# ProDoc_P1_2025-06-26.net
KiCad netlist of a schematic drawn in EasyEDA Pro
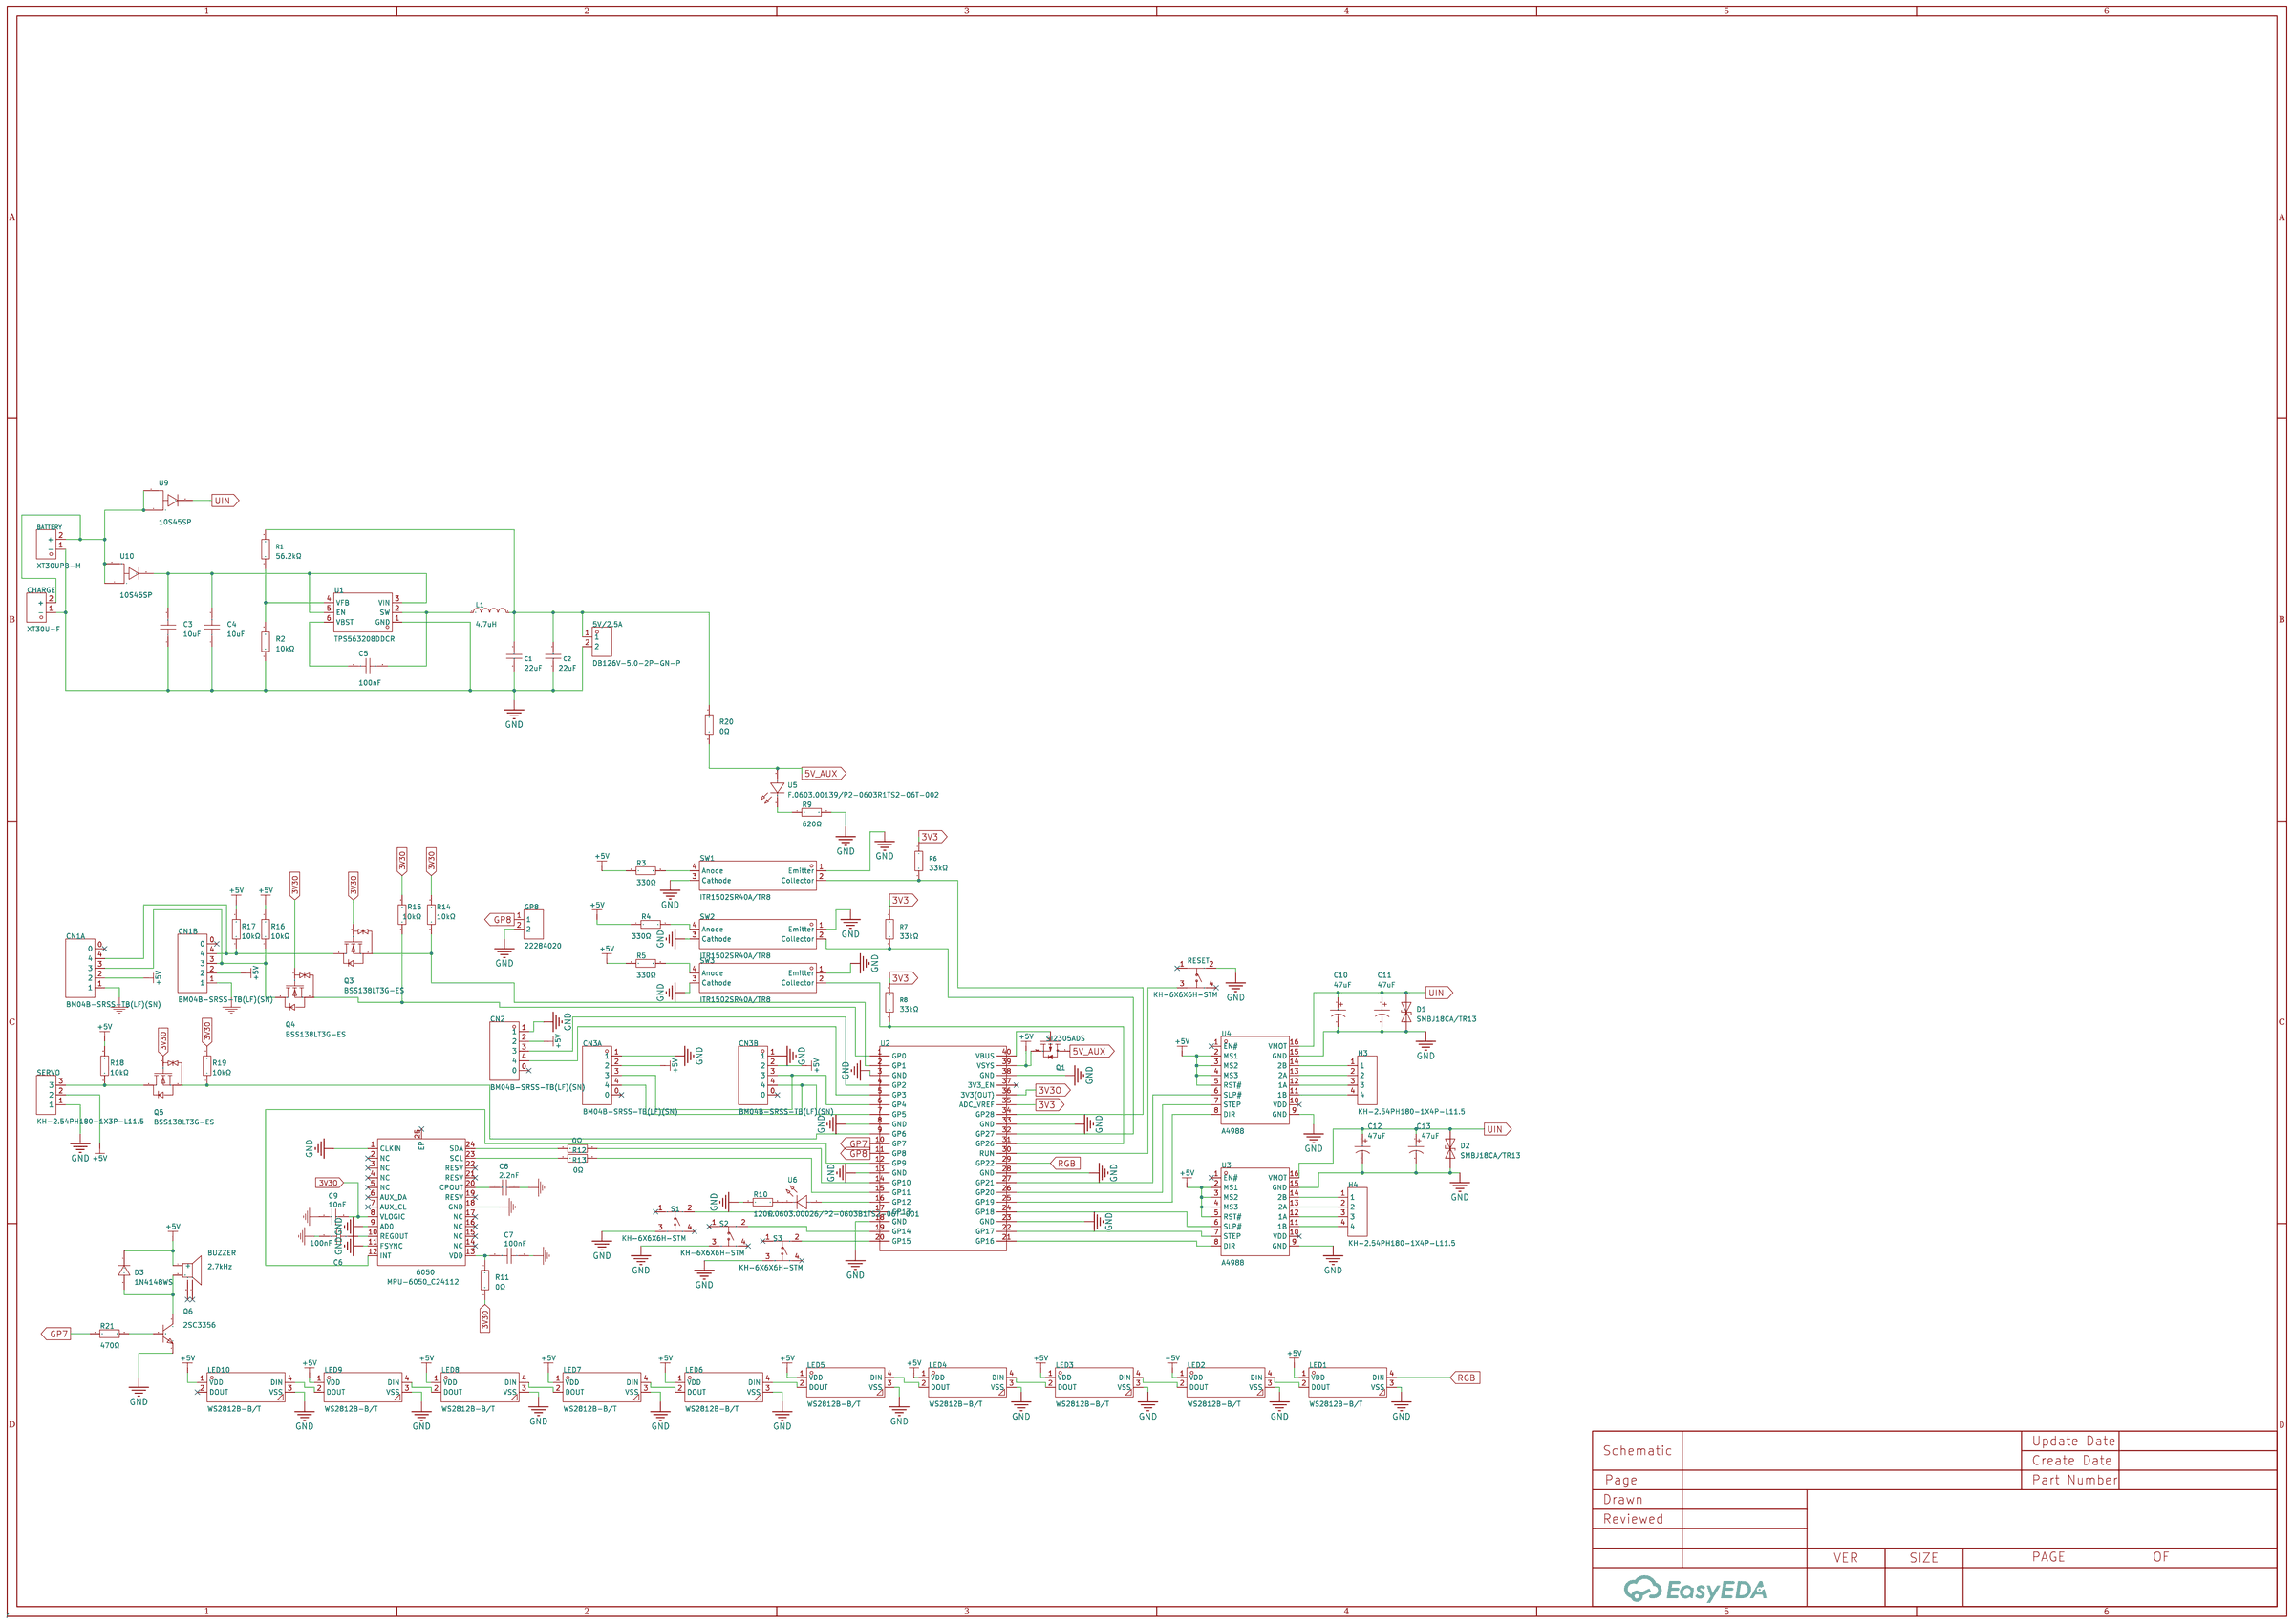
[diagram p0: schematic sheet]

(export (version "E")
  (design (tool "Eeschema 10.0.6"))
  (components
    (comp (ref "5V/2.5A")
      (value "DB126V-5.0-2P-GN-P")
      (footprint "easyedapro:CONN-TH_2P-P5.00_L7.8-W10.0")
      (fields (field (name "Manufacturer") "DORABO(地博电气)"))
      (libsource (lib "easyedapro") (part "DB126V-5.0-2P"))
    )
    (comp (ref "6050")
      (value "MPU-6050_C24112")
      (footprint "easyedapro:QFN-24_L4.0-W4.0-P0.50-BL-EP2.7")
      (fields
        (field (name "Manufacturer Part") "MPU-6050")
        (field (name "Manufacturer") "TDK InvenSense(应美盛)")
      )
      (libsource (lib "easyedapro") (part "MPU-6050_C24112"))
    )
    (comp (ref "BATTERY")
      (value "XT30UPB-M")
      (footprint "easyedapro:CONN-TH_XT30UPB-M")
      (fields (field (name "Manufacturer") "AMASS(艾迈斯)"))
      (libsource (lib "easyedapro") (part "XT30UPB-M"))
    )
    (comp (ref "BUZZER")
      (value "2.7kHz")
      (footprint "easyedapro:BUZ-SMD_4P-L8.5-W8.5-P8.50-BR")
      (fields (field (name "Manufacturer Part") "MLT-8530") (field (name "Manufacturer") "华能"))
      (libsource (lib "easyedapro") (part "MLT-8530"))
    )
    (comp (ref "C1")
      (value "22uF")
      (footprint "easyedapro:C1210")
      (fields
        (field (name "Manufacturer Part") "GRM32ER61E226KE15L")
        (field (name "Manufacturer") "muRata(村田)")
      )
      (libsource (lib "easyedapro") (part "GRM32ER61E226KE15L"))
    )
    (comp (ref "C2")
      (value "22uF")
      (footprint "easyedapro:C1210")
      (fields
        (field (name "Manufacturer Part") "GRM32ER61E226KE15L")
        (field (name "Manufacturer") "muRata(村田)")
      )
      (libsource (lib "easyedapro") (part "GRM32ER61E226KE15L"))
    )
    (comp (ref "C3")
      (value "10uF")
      (footprint "easyedapro:C1206")
      (fields
        (field (name "Manufacturer Part") "GRM31CR61E106KA12L")
        (field (name "Manufacturer") "muRata(村田)")
      )
      (libsource (lib "easyedapro") (part "GRM31CR61E106KA12L"))
    )
    (comp (ref "C4")
      (value "10uF")
      (footprint "easyedapro:C1206")
      (fields
        (field (name "Manufacturer Part") "GRM31CR61E106KA12L")
        (field (name "Manufacturer") "muRata(村田)")
      )
      (libsource (lib "easyedapro") (part "GRM31CR61E106KA12L"))
    )
    (comp (ref "C5")
      (value "100nF")
      (footprint "easyedapro:C0603")
      (fields
        (field (name "Manufacturer Part") "GRM188R71H104KA93D")
        (field (name "Manufacturer") "muRata(村田)")
      )
      (libsource (lib "easyedapro") (part "GRM188R71H104KA93D"))
    )
    (comp (ref "C6")
      (value "100nF")
      (footprint "easyedapro:C0603")
      (fields
        (field (name "Manufacturer Part") "CL10B104KB8NNNC")
        (field (name "Manufacturer") "SAMSUNG(三星)")
      )
      (libsource (lib "easyedapro") (part "100nF"))
    )
    (comp (ref "C7")
      (value "100nF")
      (footprint "easyedapro:C0603")
      (fields
        (field (name "Manufacturer Part") "CL10B104KB8NNNC")
        (field (name "Manufacturer") "SAMSUNG(三星)")
      )
      (libsource (lib "easyedapro") (part "100nF"))
    )
    (comp (ref "C8")
      (value "2.2nF")
      (footprint "easyedapro:C0603")
      (fields (field (name "Manufacturer Part") "0603B222K500NT") (field (name "Manufacturer") "FH(风华)"))
      (libsource (lib "easyedapro") (part "2.2nF"))
    )
    (comp (ref "C9")
      (value "10nF")
      (footprint "easyedapro:C0603")
      (fields
        (field (name "Manufacturer Part") "CL10B103KB8NNNC")
        (field (name "Manufacturer") "SAMSUNG(三星)")
      )
      (libsource (lib "easyedapro") (part "10nF"))
    )
    (comp (ref "C10")
      (value "47uF")
      (footprint "easyedapro:CAP-TH_BD6.3-P2.50-D1.0-FD")
      (fields
        (field (name "Manufacturer Part") "SPZ1HM470E08O00RAXXX")
        (field (name "Manufacturer") "AISHI(艾华集团)")
      )
      (libsource (lib "easyedapro") (part "SPZ1HM470E08000R"))
    )
    (comp (ref "C11")
      (value "47uF")
      (footprint "easyedapro:CAP-TH_BD6.3-P2.50-D1.0-FD")
      (fields
        (field (name "Manufacturer Part") "SPZ1HM470E08O00RAXXX")
        (field (name "Manufacturer") "AISHI(艾华集团)")
      )
      (libsource (lib "easyedapro") (part "SPZ1HM470E08000R"))
    )
    (comp (ref "C12")
      (value "47uF")
      (footprint "easyedapro:CAP-TH_BD6.3-P2.50-D1.0-FD")
      (fields
        (field (name "Manufacturer Part") "SPZ1HM470E08O00RAXXX")
        (field (name "Manufacturer") "AISHI(艾华集团)")
      )
      (libsource (lib "easyedapro") (part "SPZ1HM470E08000R"))
    )
    (comp (ref "C13")
      (value "47uF")
      (footprint "easyedapro:CAP-TH_BD6.3-P2.50-D1.0-FD")
      (fields
        (field (name "Manufacturer Part") "SPZ1HM470E08O00RAXXX")
        (field (name "Manufacturer") "AISHI(艾华集团)")
      )
      (libsource (lib "easyedapro") (part "SPZ1HM470E08000R"))
    )
    (comp (ref "CHARGE")
      (value "XT30U-F")
      (footprint "easyedapro:CONN-TH_XT30U-F")
      (fields (field (name "Manufacturer") "AMASS(艾迈斯)"))
      (libsource (lib "easyedapro") (part "XT30U-F"))
    )
    (comp (ref "CN1A")
      (value "BM04B-SRSS-TB(LF)(SN)")
      (footprint "easyedapro:CONN-SMD_BM04B-SRSS-TB")
      (fields (field (name "Manufacturer") "JST"))
      (libsource (lib "easyedapro") (part "BM04B-SRSS-TB(LF)(SN)"))
    )
    (comp (ref "CN1B")
      (value "BM04B-SRSS-TB(LF)(SN)")
      (footprint "easyedapro:CONN-SMD_BM04B-SRSS-TB")
      (fields (field (name "Manufacturer") "JST"))
      (libsource (lib "easyedapro") (part "BM04B-SRSS-TB(LF)(SN)"))
    )
    (comp (ref "CN2")
      (value "BM04B-SRSS-TB(LF)(SN)")
      (footprint "easyedapro:CONN-SMD_BM04B-SRSS-TB")
      (fields (field (name "Manufacturer") "JST"))
      (libsource (lib "") (part "BM04B-SRSS-TB(LF)(SN)_1"))
    )
    (comp (ref "CN3A")
      (value "BM04B-SRSS-TB(LF)(SN)")
      (footprint "easyedapro:CONN-SMD_BM04B-SRSS-TB")
      (fields (field (name "Manufacturer") "JST"))
      (libsource (lib "") (part "BM04B-SRSS-TB(LF)(SN)_1"))
    )
    (comp (ref "CN3B")
      (value "BM04B-SRSS-TB(LF)(SN)")
      (footprint "easyedapro:CONN-SMD_BM04B-SRSS-TB")
      (fields (field (name "Manufacturer") "JST"))
      (libsource (lib "") (part "BM04B-SRSS-TB(LF)(SN)_1"))
    )
    (comp (ref "D1")
      (value "SMBJ18CA/TR13")
      (footprint "easyedapro:SMB_L4.6-W3.6-LS5.3-BI")
      (fields (field (name "Manufacturer") "Brightking(君耀电子)"))
      (libsource (lib "easyedapro") (part "SMBJ18CA-C78413"))
    )
    (comp (ref "D2")
      (value "SMBJ18CA/TR13")
      (footprint "easyedapro:SMB_L4.6-W3.6-LS5.3-BI")
      (fields (field (name "Manufacturer") "Brightking(君耀电子)"))
      (libsource (lib "easyedapro") (part "SMBJ18CA-C78413"))
    )
    (comp (ref "D3")
      (value "1N4148WS")
      (footprint "easyedapro:SOD-323_L1.8-W1.3-LS2.5-RD")
      (fields (field (name "Manufacturer") "CJ(江苏长电/长晶)"))
      (libsource (lib "easyedapro") (part "1N4148WS T4"))
    )
    (comp (ref "GP8")
      (value "22284020")
      (footprint "easyedapro:HDR-TH_2P-P2.54-V-M-1")
      (fields (field (name "Manufacturer") "MOLEX"))
      (libsource (lib "easyedapro") (part "22-28-4020"))
    )
    (comp (ref "H3")
      (value "KH-2.54PH180-1X4P-L11.5")
      (footprint "easyedapro:HDR-TH_4P-P2.54-V-M")
      (fields (field (name "Manufacturer") "kinghelm(金航标)"))
      (libsource (lib "easyedapro") (part "KH-2.54PH180-1X4P-L11.5"))
    )
    (comp (ref "H4")
      (value "KH-2.54PH180-1X4P-L11.5")
      (footprint "easyedapro:HDR-TH_4P-P2.54-V-M")
      (fields (field (name "Manufacturer") "kinghelm(金航标)"))
      (libsource (lib "easyedapro") (part "KH-2.54PH180-1X4P-L11.5"))
    )
    (comp (ref "L1")
      (value "4.7uH")
      (footprint "easyedapro:IND-SMD_L7.0-W6.6")
      (fields (field (name "Manufacturer Part") "FXL0630-4R7-M") (field (name "Manufacturer") "cjiang(长江微电)"))
      (libsource (lib "easyedapro") (part "FXL0630-4R7-M"))
    )
    (comp (ref "LED1")
      (value "WS2812B-B/T")
      (footprint "easyedapro:LED-SMD_4P-L5.0-W5.0-TL_WS2812B-B")
      (fields (field (name "Manufacturer") "worldsemi"))
      (libsource (lib "easyedapro") (part "WS2812B-B/W"))
    )
    (comp (ref "LED2")
      (value "WS2812B-B/T")
      (footprint "easyedapro:LED-SMD_4P-L5.0-W5.0-TL_WS2812B-B")
      (fields (field (name "Manufacturer") "worldsemi"))
      (libsource (lib "easyedapro") (part "WS2812B-B/W"))
    )
    (comp (ref "LED3")
      (value "WS2812B-B/T")
      (footprint "easyedapro:LED-SMD_4P-L5.0-W5.0-TL_WS2812B-B")
      (fields (field (name "Manufacturer") "worldsemi"))
      (libsource (lib "easyedapro") (part "WS2812B-B/W"))
    )
    (comp (ref "LED4")
      (value "WS2812B-B/T")
      (footprint "easyedapro:LED-SMD_4P-L5.0-W5.0-TL_WS2812B-B")
      (fields (field (name "Manufacturer") "worldsemi"))
      (libsource (lib "easyedapro") (part "WS2812B-B/W"))
    )
    (comp (ref "LED5")
      (value "WS2812B-B/T")
      (footprint "easyedapro:LED-SMD_4P-L5.0-W5.0-TL_WS2812B-B")
      (fields (field (name "Manufacturer") "worldsemi"))
      (libsource (lib "easyedapro") (part "WS2812B-B/W"))
    )
    (comp (ref "LED6")
      (value "WS2812B-B/T")
      (footprint "easyedapro:LED-SMD_4P-L5.0-W5.0-TL_WS2812B-B")
      (fields (field (name "Manufacturer") "worldsemi"))
      (libsource (lib "easyedapro") (part "WS2812B-B/W"))
    )
    (comp (ref "LED7")
      (value "WS2812B-B/T")
      (footprint "easyedapro:LED-SMD_4P-L5.0-W5.0-TL_WS2812B-B")
      (fields (field (name "Manufacturer") "worldsemi"))
      (libsource (lib "easyedapro") (part "WS2812B-B/W"))
    )
    (comp (ref "LED8")
      (value "WS2812B-B/T")
      (footprint "easyedapro:LED-SMD_4P-L5.0-W5.0-TL_WS2812B-B")
      (fields (field (name "Manufacturer") "worldsemi"))
      (libsource (lib "easyedapro") (part "WS2812B-B/W"))
    )
    (comp (ref "LED9")
      (value "WS2812B-B/T")
      (footprint "easyedapro:LED-SMD_4P-L5.0-W5.0-TL_WS2812B-B")
      (fields (field (name "Manufacturer") "worldsemi"))
      (libsource (lib "easyedapro") (part "WS2812B-B/W"))
    )
    (comp (ref "LED10")
      (value "WS2812B-B/T")
      (footprint "easyedapro:LED-SMD_4P-L5.0-W5.0-TL_WS2812B-B")
      (fields (field (name "Manufacturer") "worldsemi"))
      (libsource (lib "easyedapro") (part "WS2812B-B/W"))
    )
    (comp (ref "Q1")
      (value "SI2305ADS")
      (footprint "easyedapro:SOT-23-3_L2.9-W1.3-P1.90-LS2.4-BR")
      (fields (field (name "Manufacturer") "TECH PUBLIC(台舟)"))
      (libsource (lib "easyedapro") (part "SI2305ADS"))
    )
    (comp (ref "Q3")
      (value "BSS138LT3G-ES")
      (footprint "easyedapro:SOT-23-3_L2.9-W1.3-P1.90-LS2.4-BR")
      (fields (field (name "Manufacturer") "ElecSuper(静芯微)"))
      (libsource (lib "easyedapro") (part "BSS138LT3G-ES"))
    )
    (comp (ref "Q4")
      (value "BSS138LT3G-ES")
      (footprint "easyedapro:SOT-23-3_L2.9-W1.3-P1.90-LS2.4-BR")
      (fields (field (name "Manufacturer") "ElecSuper(静芯微)"))
      (libsource (lib "easyedapro") (part "BSS138LT3G-ES"))
    )
    (comp (ref "Q5")
      (value "BSS138LT3G-ES")
      (footprint "easyedapro:SOT-23-3_L2.9-W1.3-P1.90-LS2.4-BR")
      (fields (field (name "Manufacturer") "ElecSuper(静芯微)"))
      (libsource (lib "easyedapro") (part "BSS138LT3G-ES"))
    )
    (comp (ref "Q6")
      (value "2SC3356")
      (footprint "easyedapro:SOT-23-3_L2.9-W1.3-P1.90-LS2.4-BR")
      (fields (field (name "Manufacturer") "宏嘉诚"))
      (libsource (lib "easyedapro") (part "2SC3356_C28646266"))
    )
    (comp (ref "R1")
      (value "56.2kΩ")
      (footprint "easyedapro:R0402")
      (fields
        (field (name "Manufacturer Part") "0402WGF5622TCE")
        (field (name "Manufacturer") "UNI-ROYAL(厚声)")
      )
      (libsource (lib "easyedapro") (part "0402WGF5622TCE"))
    )
    (comp (ref "R2")
      (value "10kΩ")
      (footprint "easyedapro:R0402")
      (fields
        (field (name "Manufacturer Part") "0402WGF1002TCE")
        (field (name "Manufacturer") "UNI-ROYAL(厚声)")
      )
      (libsource (lib "easyedapro") (part "0402WGF1002TCE"))
    )
    (comp (ref "R3")
      (value "330Ω")
      (footprint "easyedapro:R0603")
      (fields
        (field (name "Manufacturer Part") "0603WAF3300T5E")
        (field (name "Manufacturer") "UNI-ROYAL(厚声)")
      )
      (libsource (lib "easyedapro") (part "0603WAF3300T5E"))
    )
    (comp (ref "R4")
      (value "330Ω")
      (footprint "easyedapro:R0603")
      (fields
        (field (name "Manufacturer Part") "0603WAF3300T5E")
        (field (name "Manufacturer") "UNI-ROYAL(厚声)")
      )
      (libsource (lib "easyedapro") (part "0603WAF3300T5E"))
    )
    (comp (ref "R5")
      (value "330Ω")
      (footprint "easyedapro:R0603")
      (fields
        (field (name "Manufacturer Part") "0603WAF3300T5E")
        (field (name "Manufacturer") "UNI-ROYAL(厚声)")
      )
      (libsource (lib "easyedapro") (part "0603WAF3300T5E"))
    )
    (comp (ref "R6")
      (value "33kΩ")
      (footprint "easyedapro:R0603")
      (fields
        (field (name "Manufacturer Part") "0603WAF3302T5E")
        (field (name "Manufacturer") "UNI-ROYAL(厚声)")
      )
      (libsource (lib "easyedapro") (part "0603WAF3302T5E"))
    )
    (comp (ref "R7")
      (value "33kΩ")
      (footprint "easyedapro:R0603")
      (fields
        (field (name "Manufacturer Part") "0603WAF3302T5E")
        (field (name "Manufacturer") "UNI-ROYAL(厚声)")
      )
      (libsource (lib "easyedapro") (part "0603WAF3302T5E"))
    )
    (comp (ref "R8")
      (value "33kΩ")
      (footprint "easyedapro:R0603")
      (fields
        (field (name "Manufacturer Part") "0603WAF3302T5E")
        (field (name "Manufacturer") "UNI-ROYAL(厚声)")
      )
      (libsource (lib "easyedapro") (part "0603WAF3302T5E"))
    )
    (comp (ref "R9")
      (value "620Ω")
      (footprint "easyedapro:R0603")
      (fields (field (name "Manufacturer Part") "RC0603FR-07620RL") (field (name "Manufacturer") "YAGEO(国巨)"))
      (libsource (lib "easyedapro") (part "RC0603FR-07620RL"))
    )
    (comp (ref "R10")
      (value "120Ω")
      (footprint "easyedapro:R0603")
      (fields (field (name "Manufacturer Part") "RC0603FR-07120RL") (field (name "Manufacturer") "YAGEO(国巨)"))
      (libsource (lib "easyedapro") (part "RC0603FR-07120RL"))
    )
    (comp (ref "R11")
      (value "0Ω")
      (footprint "easyedapro:R0603")
      (fields
        (field (name "Manufacturer Part") "0603WAJ0000T5E")
        (field (name "Manufacturer") "UNI-ROYAL(厚声)")
      )
      (libsource (lib "easyedapro") (part "0Ω"))
    )
    (comp (ref "R12")
      (value "0Ω")
      (footprint "easyedapro:R0603")
      (fields
        (field (name "Manufacturer Part") "0603WAJ0000T5E")
        (field (name "Manufacturer") "UNI-ROYAL(厚声)")
      )
      (libsource (lib "easyedapro") (part "0Ω"))
    )
    (comp (ref "R13")
      (value "0Ω")
      (footprint "easyedapro:R0603")
      (fields
        (field (name "Manufacturer Part") "0603WAJ0000T5E")
        (field (name "Manufacturer") "UNI-ROYAL(厚声)")
      )
      (libsource (lib "easyedapro") (part "0Ω"))
    )
    (comp (ref "R14")
      (value "10kΩ")
      (footprint "easyedapro:R0603")
      (fields (field (name "Manufacturer Part") "AC0603FR-0710KL") (field (name "Manufacturer") "YAGEO(国巨)"))
      (libsource (lib "easyedapro") (part "10kΩ"))
    )
    (comp (ref "R15")
      (value "10kΩ")
      (footprint "easyedapro:R0603")
      (fields (field (name "Manufacturer Part") "AC0603FR-0710KL") (field (name "Manufacturer") "YAGEO(国巨)"))
      (libsource (lib "easyedapro") (part "10kΩ"))
    )
    (comp (ref "R16")
      (value "10kΩ")
      (footprint "easyedapro:R0603")
      (fields (field (name "Manufacturer Part") "AC0603FR-0710KL") (field (name "Manufacturer") "YAGEO(国巨)"))
      (libsource (lib "easyedapro") (part "10kΩ"))
    )
    (comp (ref "R17")
      (value "10kΩ")
      (footprint "easyedapro:R0603")
      (fields (field (name "Manufacturer Part") "AC0603FR-0710KL") (field (name "Manufacturer") "YAGEO(国巨)"))
      (libsource (lib "easyedapro") (part "10kΩ"))
    )
    (comp (ref "R18")
      (value "10kΩ")
      (footprint "easyedapro:R0603")
      (fields (field (name "Manufacturer Part") "AC0603FR-0710KL") (field (name "Manufacturer") "YAGEO(国巨)"))
      (libsource (lib "easyedapro") (part "10kΩ"))
    )
    (comp (ref "R19")
      (value "10kΩ")
      (footprint "easyedapro:R0603")
      (fields (field (name "Manufacturer Part") "AC0603FR-0710KL") (field (name "Manufacturer") "YAGEO(国巨)"))
      (libsource (lib "easyedapro") (part "10kΩ"))
    )
    (comp (ref "R20")
      (value "0Ω")
      (footprint "easyedapro:R0603")
      (fields
        (field (name "Manufacturer Part") "0603WAJ0000T5E")
        (field (name "Manufacturer") "UNI-ROYAL(厚声)")
      )
      (libsource (lib "easyedapro") (part "0Ω"))
    )
    (comp (ref "R21")
      (value "470Ω")
      (footprint "easyedapro:R0603")
      (fields
        (field (name "Manufacturer Part") "0603WAF4700T5E")
        (field (name "Manufacturer") "UNI-ROYAL(厚声)")
      )
      (libsource (lib "easyedapro") (part "0603WAF4700T5E"))
    )
    (comp (ref "RESET")
      (value "KH-6X6X6H-STM")
      (footprint "easyedapro:SW-SMD_4P-L6.0-W6.0-P4.50-LS9.0-3")
      (fields (field (name "Manufacturer") "kinghelm(金航标)"))
      (libsource (lib "easyedapro") (part "KH-6X6X6H-STM"))
    )
    (comp (ref "S1")
      (value "KH-6X6X6H-STM")
      (footprint "easyedapro:SW-SMD_4P-L6.0-W6.0-P4.50-LS9.0-3")
      (fields (field (name "Manufacturer") "kinghelm(金航标)"))
      (libsource (lib "easyedapro") (part "KH-6X6X6H-STM"))
    )
    (comp (ref "S2")
      (value "KH-6X6X6H-STM")
      (footprint "easyedapro:SW-SMD_4P-L6.0-W6.0-P4.50-LS9.0-3")
      (fields (field (name "Manufacturer") "kinghelm(金航标)"))
      (libsource (lib "easyedapro") (part "KH-6X6X6H-STM"))
    )
    (comp (ref "S3")
      (value "KH-6X6X6H-STM")
      (footprint "easyedapro:SW-SMD_4P-L6.0-W6.0-P4.50-LS9.0-3")
      (fields (field (name "Manufacturer") "kinghelm(金航标)"))
      (libsource (lib "easyedapro") (part "KH-6X6X6H-STM"))
    )
    (comp (ref "SERVO")
      (value "KH-2.54PH180-1X3P-L11.5")
      (footprint "easyedapro:HDR-TH_3P-P2.54-V-M")
      (fields (field (name "Manufacturer") "kinghelm(金航标)"))
      (libsource (lib "easyedapro") (part "KH-2.54PH180-1X3P-L11.5"))
    )
    (comp (ref "SW1")
      (value "ITR1502SR40A/TR8")
      (footprint "easyedapro:SW-SMD_4P-L4.0-W3.0_ITR1502SR40A-TR8")
      (fields (field (name "Manufacturer") "EVERLIGHT(亿光)"))
      (libsource (lib "easyedapro") (part "ITR1502SR40A/TR8"))
    )
    (comp (ref "SW2")
      (value "ITR1502SR40A/TR8")
      (footprint "easyedapro:SW-SMD_4P-L4.0-W3.0_ITR1502SR40A-TR8")
      (fields (field (name "Manufacturer") "EVERLIGHT(亿光)"))
      (libsource (lib "easyedapro") (part "ITR1502SR40A/TR8"))
    )
    (comp (ref "SW3")
      (value "ITR1502SR40A/TR8")
      (footprint "easyedapro:SW-SMD_4P-L4.0-W3.0_ITR1502SR40A-TR8")
      (fields (field (name "Manufacturer") "EVERLIGHT(亿光)"))
      (libsource (lib "easyedapro") (part "ITR1502SR40A/TR8"))
    )
    (comp (ref "U1")
      (value "TPS563208DDCR")
      (footprint "easyedapro:TSOT-23-6_L2.9-W1.6-P0.95-LS2.8-BL")
      (fields (field (name "Manufacturer") "TI(德州仪器)"))
      (libsource (lib "easyedapro") (part "TPS563208DDCR"))
    )
    (comp (ref "U2")
      (value "~")
      (footprint "easyedapro:RPI_PICO_DIL")
      (description "Raspberry pi pico in DIL")
      (libsource (lib "easyedapro") (part "RPI_PICO_DIL"))
    )
    (comp (ref "U3")
      (value "A4988")
      (footprint "easyedapro:DIP-16_L20.3-W15.2-P2.54_LS12.7_A4988")
      (libsource (lib "easyedapro") (part "A4988"))
    )
    (comp (ref "U4")
      (value "A4988")
      (footprint "easyedapro:DIP-16_L20.3-W15.2-P2.54_LS12.7_A4988")
      (libsource (lib "easyedapro") (part "A4988"))
    )
    (comp (ref "U5")
      (value "F.0603.00139/P2-0603R1TS2-06T-002")
      (footprint "easyedapro:LED0603-RD")
      (fields (field (name "Manufacturer") "TUOZHAN(拓展光电)"))
      (libsource (lib "easyedapro") (part "F.0603.00139/P2-0603R1TS2-06T-002"))
    )
    (comp (ref "U6")
      (value "F.0603.00026/P2-0603B1TS2-06T-001")
      (footprint "easyedapro:LED0603-RD")
      (fields (field (name "Manufacturer") "TUOZHAN(拓展光电)"))
      (libsource (lib "easyedapro") (part "F.0603.00026/P2-0603B1TS2-06T-001"))
    )
    (comp (ref "U9")
      (value "10S45SP")
      (footprint "easyedapro:TO-277_3P-L5.4-W4.0-LS6.5-TR-1")
      (fields (field (name "Manufacturer") "YFW(佑风微)"))
      (libsource (lib "easyedapro") (part "10S45SP"))
    )
    (comp (ref "U10")
      (value "10S45SP")
      (footprint "easyedapro:TO-277_3P-L5.4-W4.0-LS6.5-TR-1")
      (fields (field (name "Manufacturer") "YFW(佑风微)"))
      (libsource (lib "easyedapro") (part "10S45SP"))
    )
  )
  (nets
    (net (code "1") (name "+5V") (class "Default")
      (node (ref "BUZZER") (pin "1") (pinfunction "+_1") (pintype "unspecified"))
      (node (ref "CN1A") (pin "2") (pinfunction "2_2") (pintype "unspecified"))
      (node (ref "CN1B") (pin "2") (pinfunction "2_2") (pintype "unspecified"))
      (node (ref "CN2") (pin "2") (pinfunction "2_2") (pintype "unspecified"))
      (node (ref "CN3A") (pin "2") (pinfunction "2_2") (pintype "unspecified"))
      (node (ref "CN3B") (pin "2") (pinfunction "2_2") (pintype "unspecified"))
      (node (ref "D3") (pin "1") (pinfunction "K_1") (pintype "unspecified"))
      (node (ref "LED1") (pin "1") (pinfunction "VDD_1") (pintype "unspecified"))
      (node (ref "LED10") (pin "1") (pinfunction "VDD_1") (pintype "unspecified"))
      (node (ref "LED2") (pin "1") (pinfunction "VDD_1") (pintype "unspecified"))
      (node (ref "LED3") (pin "1") (pinfunction "VDD_1") (pintype "unspecified"))
      (node (ref "LED4") (pin "1") (pinfunction "VDD_1") (pintype "unspecified"))
      (node (ref "LED5") (pin "1") (pinfunction "VDD_1") (pintype "unspecified"))
      (node (ref "LED6") (pin "1") (pinfunction "VDD_1") (pintype "unspecified"))
      (node (ref "LED7") (pin "1") (pinfunction "VDD_1") (pintype "unspecified"))
      (node (ref "LED8") (pin "1") (pinfunction "VDD_1") (pintype "unspecified"))
      (node (ref "LED9") (pin "1") (pinfunction "VDD_1") (pintype "unspecified"))
      (node (ref "Q1") (pin "2") (pinfunction "S_2") (pintype "unspecified"))
      (node (ref "R16") (pin "2") (pinfunction "2_2") (pintype "input"))
      (node (ref "R17") (pin "2") (pinfunction "2_2") (pintype "input"))
      (node (ref "R18") (pin "2") (pinfunction "2_2") (pintype "input"))
      (node (ref "R3") (pin "1") (pinfunction "1_1") (pintype "input"))
      (node (ref "R4") (pin "1") (pinfunction "1_1") (pintype "input"))
      (node (ref "R5") (pin "1") (pinfunction "1_1") (pintype "input"))
      (node (ref "SERVO") (pin "2") (pinfunction "2_2") (pintype "unspecified"))
      (node (ref "U2") (pin "39") (pinfunction "VSYS_39") (pintype "input"))
      (node (ref "U3") (pin "2") (pinfunction "MS1_2") (pintype "unspecified"))
      (node (ref "U3") (pin "3") (pinfunction "MS2_3") (pintype "unspecified"))
      (node (ref "U3") (pin "4") (pinfunction "MS3_4") (pintype "unspecified"))
      (node (ref "U3") (pin "5") (pinfunction "RST#_5") (pintype "unspecified"))
      (node (ref "U4") (pin "2") (pinfunction "MS1_2") (pintype "unspecified"))
      (node (ref "U4") (pin "3") (pinfunction "MS2_3") (pintype "unspecified"))
      (node (ref "U4") (pin "4") (pinfunction "MS3_4") (pintype "unspecified"))
      (node (ref "U4") (pin "5") (pinfunction "RST#_5") (pintype "unspecified"))
    )
    (net (code "2") (name "3V3") (class "Default")
      (node (ref "R6") (pin "1") (pinfunction "1_1") (pintype "input"))
      (node (ref "R7") (pin "1") (pinfunction "1_1") (pintype "input"))
      (node (ref "R8") (pin "2") (pinfunction "2_2") (pintype "input"))
      (node (ref "U2") (pin "35") (pinfunction "ADC_VREF_35") (pintype "input"))
    )
    (net (code "3") (name "3V3O") (class "Default")
      (node (ref "6050") (pin "8") (pinfunction "VLOGIC_8") (pintype "unspecified"))
      (node (ref "C9") (pin "2") (pinfunction "2_2") (pintype "input"))
      (node (ref "Q3") (pin "1") (pinfunction "G_1") (pintype "unspecified"))
      (node (ref "Q4") (pin "1") (pinfunction "G_1") (pintype "unspecified"))
      (node (ref "Q5") (pin "1") (pinfunction "G_1") (pintype "unspecified"))
      (node (ref "R11") (pin "2") (pinfunction "2_2") (pintype "input"))
      (node (ref "R14") (pin "2") (pinfunction "2_2") (pintype "input"))
      (node (ref "R15") (pin "2") (pinfunction "2_2") (pintype "input"))
      (node (ref "R19") (pin "2") (pinfunction "2_2") (pintype "input"))
      (node (ref "U2") (pin "36") (pinfunction "3V3(OUT)_36") (pintype "input"))
    )
    (net (code "4") (name "5V_AUX") (class "Default")
      (node (ref "Q1") (pin "3") (pinfunction "D_3") (pintype "unspecified"))
      (node (ref "R20") (pin "2") (pinfunction "2_2") (pintype "input"))
      (node (ref "U5") (pin "2") (pinfunction "A_2") (pintype "unspecified"))
    )
    (net (code "5") (name "GND") (class "Default")
      (node (ref "5V/2.5A") (pin "2") (pinfunction "2_2") (pintype "unspecified"))
      (node (ref "6050") (pin "1") (pinfunction "CLKIN_1") (pintype "unspecified"))
      (node (ref "6050") (pin "11") (pinfunction "FSYNC_11") (pintype "unspecified"))
      (node (ref "6050") (pin "18") (pinfunction "GND_18") (pintype "unspecified"))
      (node (ref "6050") (pin "9") (pinfunction "AD0_9") (pintype "unspecified"))
      (node (ref "BATTERY") (pin "1") (pinfunction "-_1") (pintype "input"))
      (node (ref "C1") (pin "2") (pinfunction "2_2") (pintype "input"))
      (node (ref "C10") (pin "2") (pinfunction "2_2") (pintype "input"))
      (node (ref "C11") (pin "2") (pinfunction "2_2") (pintype "input"))
      (node (ref "C12") (pin "2") (pinfunction "2_2") (pintype "input"))
      (node (ref "C13") (pin "2") (pinfunction "2_2") (pintype "input"))
      (node (ref "C2") (pin "1") (pinfunction "1_1") (pintype "input"))
      (node (ref "C3") (pin "1") (pinfunction "1_1") (pintype "unspecified"))
      (node (ref "C4") (pin "1") (pinfunction "1_1") (pintype "unspecified"))
      (node (ref "C6") (pin "2") (pinfunction "2_2") (pintype "unspecified"))
      (node (ref "C7") (pin "1") (pinfunction "1_1") (pintype "unspecified"))
      (node (ref "C8") (pin "2") (pinfunction "2_2") (pintype "input"))
      (node (ref "C9") (pin "1") (pinfunction "1_1") (pintype "input"))
      (node (ref "CHARGE") (pin "1") (pinfunction "-_1") (pintype "unspecified"))
      (node (ref "CN1A") (pin "1") (pinfunction "1_1") (pintype "unspecified"))
      (node (ref "CN1B") (pin "1") (pinfunction "1_1") (pintype "unspecified"))
      (node (ref "CN2") (pin "1") (pinfunction "1_1") (pintype "unspecified"))
      (node (ref "CN3A") (pin "1") (pinfunction "1_1") (pintype "unspecified"))
      (node (ref "CN3B") (pin "1") (pinfunction "1_1") (pintype "unspecified"))
      (node (ref "D1") (pin "2") (pinfunction "2_2") (pintype "unspecified"))
      (node (ref "D2") (pin "1") (pinfunction "1_1") (pintype "unspecified"))
      (node (ref "GP8") (pin "2") (pinfunction "2_2") (pintype "unspecified"))
      (node (ref "LED1") (pin "3") (pinfunction "VSS_3") (pintype "unspecified"))
      (node (ref "LED10") (pin "3") (pinfunction "VSS_3") (pintype "unspecified"))
      (node (ref "LED2") (pin "3") (pinfunction "VSS_3") (pintype "unspecified"))
      (node (ref "LED3") (pin "3") (pinfunction "VSS_3") (pintype "unspecified"))
      (node (ref "LED4") (pin "3") (pinfunction "VSS_3") (pintype "unspecified"))
      (node (ref "LED5") (pin "3") (pinfunction "VSS_3") (pintype "unspecified"))
      (node (ref "LED6") (pin "3") (pinfunction "VSS_3") (pintype "unspecified"))
      (node (ref "LED7") (pin "3") (pinfunction "VSS_3") (pintype "unspecified"))
      (node (ref "LED8") (pin "3") (pinfunction "VSS_3") (pintype "unspecified"))
      (node (ref "LED9") (pin "3") (pinfunction "VSS_3") (pintype "unspecified"))
      (node (ref "Q6") (pin "2") (pinfunction "E_2") (pintype "input"))
      (node (ref "R10") (pin "1") (pinfunction "1_1") (pintype "input"))
      (node (ref "R2") (pin "1") (pinfunction "1_1") (pintype "input"))
      (node (ref "R9") (pin "2") (pinfunction "2_2") (pintype "input"))
      (node (ref "RESET") (pin "2") (pinfunction "B_2") (pintype "unspecified"))
      (node (ref "S1") (pin "3") (pinfunction "C_3") (pintype "unspecified"))
      (node (ref "S2") (pin "3") (pinfunction "C_3") (pintype "unspecified"))
      (node (ref "S3") (pin "3") (pinfunction "C_3") (pintype "unspecified"))
      (node (ref "SERVO") (pin "1") (pinfunction "1_1") (pintype "unspecified"))
      (node (ref "SW1") (pin "1") (pinfunction "Emitter_1") (pintype "unspecified"))
      (node (ref "SW1") (pin "3") (pinfunction "Cathode_3") (pintype "unspecified"))
      (node (ref "SW2") (pin "1") (pinfunction "Emitter_1") (pintype "unspecified"))
      (node (ref "SW2") (pin "3") (pinfunction "Cathode_3") (pintype "unspecified"))
      (node (ref "SW3") (pin "1") (pinfunction "Emitter_1") (pintype "unspecified"))
      (node (ref "SW3") (pin "3") (pinfunction "Cathode_3") (pintype "unspecified"))
      (node (ref "U1") (pin "1") (pinfunction "GND_1") (pintype "unspecified"))
      (node (ref "U2") (pin "13") (pinfunction "GND_13") (pintype "input"))
      (node (ref "U2") (pin "18") (pinfunction "GND_18") (pintype "input"))
      (node (ref "U2") (pin "23") (pinfunction "GND_23") (pintype "input"))
      (node (ref "U2") (pin "28") (pinfunction "GND_28") (pintype "input"))
      (node (ref "U2") (pin "3") (pinfunction "GND_3") (pintype "input"))
      (node (ref "U2") (pin "33") (pinfunction "GND_33") (pintype "input"))
      (node (ref "U2") (pin "38") (pinfunction "GND_38") (pintype "input"))
      (node (ref "U2") (pin "8") (pinfunction "GND_8") (pintype "input"))
      (node (ref "U3") (pin "15") (pinfunction "GND_15") (pintype "unspecified"))
      (node (ref "U3") (pin "9") (pinfunction "GND_9") (pintype "unspecified"))
      (node (ref "U4") (pin "15") (pinfunction "GND_15") (pintype "unspecified"))
      (node (ref "U4") (pin "9") (pinfunction "GND_9") (pintype "unspecified"))
    )
    (net (code "6") (name "GP7") (class "Default")
      (node (ref "R21") (pin "1") (pinfunction "1_1") (pintype "input"))
      (node (ref "U2") (pin "10") (pinfunction "GP7_10") (pintype "input"))
    )
    (net (code "7") (name "GP8") (class "Default")
      (node (ref "GP8") (pin "1") (pinfunction "1_1") (pintype "unspecified"))
      (node (ref "U2") (pin "11") (pinfunction "GP8_11") (pintype "input"))
    )
    (net (code "8") (name "Net-(5V/2.5A-Pad1)") (class "Default")
      (node (ref "5V/2.5A") (pin "1") (pinfunction "1_1") (pintype "unspecified"))
      (node (ref "C1") (pin "1") (pinfunction "1_1") (pintype "input"))
      (node (ref "C2") (pin "2") (pinfunction "2_2") (pintype "input"))
      (node (ref "L1") (pin "2") (pinfunction "2_2") (pintype "unspecified"))
      (node (ref "R1") (pin "2") (pinfunction "2_2") (pintype "input"))
      (node (ref "R20") (pin "1") (pinfunction "1_1") (pintype "input"))
    )
    (net (code "9") (name "Net-(6050-CPOUT)") (class "Default")
      (node (ref "6050") (pin "20") (pinfunction "CPOUT_20") (pintype "unspecified"))
      (node (ref "C8") (pin "1") (pinfunction "1_1") (pintype "input"))
    )
    (net (code "10") (name "Net-(6050-INT)") (class "Default")
      (node (ref "6050") (pin "12") (pinfunction "INT_12") (pintype "unspecified"))
      (node (ref "U2") (pin "12") (pinfunction "GP9_12") (pintype "input"))
    )
    (net (code "11") (name "Net-(6050-REGOUT)") (class "Default")
      (node (ref "6050") (pin "10") (pinfunction "REGOUT_10") (pintype "unspecified"))
      (node (ref "C6") (pin "1") (pinfunction "1_1") (pintype "unspecified"))
    )
    (net (code "12") (name "Net-(6050-SCL)") (class "Default")
      (node (ref "6050") (pin "23") (pinfunction "SCL_23") (pintype "unspecified"))
      (node (ref "R13") (pin "1") (pinfunction "1_1") (pintype "input"))
    )
    (net (code "13") (name "Net-(6050-SDA)") (class "Default")
      (node (ref "6050") (pin "24") (pinfunction "SDA_24") (pintype "unspecified"))
      (node (ref "R12") (pin "1") (pinfunction "1_1") (pintype "input"))
    )
    (net (code "14") (name "Net-(6050-VDD)") (class "Default")
      (node (ref "6050") (pin "13") (pinfunction "VDD_13") (pintype "unspecified"))
      (node (ref "C7") (pin "2") (pinfunction "2_2") (pintype "unspecified"))
      (node (ref "R11") (pin "1") (pinfunction "1_1") (pintype "input"))
    )
    (net (code "15") (name "Net-(BATTERY-+)") (class "Default")
      (node (ref "BATTERY") (pin "2") (pinfunction "+_2") (pintype "input"))
      (node (ref "CHARGE") (pin "2") (pinfunction "+_2") (pintype "unspecified"))
      (node (ref "U10") (pin "1") (pinfunction "A_1") (pintype "unspecified"))
      (node (ref "U10") (pin "2") (pinfunction "A_2") (pintype "unspecified"))
      (node (ref "U9") (pin "1") (pinfunction "A_1") (pintype "unspecified"))
      (node (ref "U9") (pin "2") (pinfunction "A_2") (pintype "unspecified"))
    )
    (net (code "16") (name "Net-(D3-A)") (class "Default")
      (node (ref "BUZZER") (pin "2") (pinfunction "2_2") (pintype "unspecified"))
      (node (ref "D3") (pin "2") (pinfunction "A_2") (pintype "unspecified"))
      (node (ref "Q6") (pin "3") (pinfunction "C_3") (pintype "input"))
    )
    (net (code "17") (name "Net-(LED1-DOUT)") (class "Default")
      (node (ref "LED1") (pin "2") (pinfunction "DOUT_2") (pintype "unspecified"))
      (node (ref "LED2") (pin "4") (pinfunction "DIN_4") (pintype "unspecified"))
    )
    (net (code "18") (name "Net-(LED2-DOUT)") (class "Default")
      (node (ref "LED2") (pin "2") (pinfunction "DOUT_2") (pintype "unspecified"))
      (node (ref "LED3") (pin "4") (pinfunction "DIN_4") (pintype "unspecified"))
    )
    (net (code "19") (name "Net-(LED3-DOUT)") (class "Default")
      (node (ref "LED3") (pin "2") (pinfunction "DOUT_2") (pintype "unspecified"))
      (node (ref "LED4") (pin "4") (pinfunction "DIN_4") (pintype "unspecified"))
    )
    (net (code "20") (name "Net-(LED4-DOUT)") (class "Default")
      (node (ref "LED4") (pin "2") (pinfunction "DOUT_2") (pintype "unspecified"))
      (node (ref "LED5") (pin "4") (pinfunction "DIN_4") (pintype "unspecified"))
    )
    (net (code "21") (name "Net-(LED5-DOUT)") (class "Default")
      (node (ref "LED5") (pin "2") (pinfunction "DOUT_2") (pintype "unspecified"))
      (node (ref "LED6") (pin "4") (pinfunction "DIN_4") (pintype "unspecified"))
    )
    (net (code "22") (name "Net-(LED6-DOUT)") (class "Default")
      (node (ref "LED6") (pin "2") (pinfunction "DOUT_2") (pintype "unspecified"))
      (node (ref "LED7") (pin "4") (pinfunction "DIN_4") (pintype "unspecified"))
    )
    (net (code "23") (name "Net-(LED7-DOUT)") (class "Default")
      (node (ref "LED7") (pin "2") (pinfunction "DOUT_2") (pintype "unspecified"))
      (node (ref "LED8") (pin "4") (pinfunction "DIN_4") (pintype "unspecified"))
    )
    (net (code "24") (name "Net-(LED8-DOUT)") (class "Default")
      (node (ref "LED8") (pin "2") (pinfunction "DOUT_2") (pintype "unspecified"))
      (node (ref "LED9") (pin "4") (pinfunction "DIN_4") (pintype "unspecified"))
    )
    (net (code "25") (name "Net-(LED10-DIN)") (class "Default")
      (node (ref "LED10") (pin "4") (pinfunction "DIN_4") (pintype "unspecified"))
      (node (ref "LED9") (pin "2") (pinfunction "DOUT_2") (pintype "unspecified"))
    )
    (net (code "26") (name "Net-(Q1-G)") (class "Default")
      (node (ref "Q1") (pin "1") (pinfunction "G_1") (pintype "unspecified"))
      (node (ref "U2") (pin "40") (pinfunction "VBUS_40") (pintype "input"))
    )
    (net (code "27") (name "Net-(Q3-D)") (class "Default")
      (node (ref "CN1A") (pin "4") (pinfunction "4_4") (pintype "unspecified"))
      (node (ref "CN1B") (pin "4") (pinfunction "4_4") (pintype "unspecified"))
      (node (ref "Q3") (pin "3") (pinfunction "D_3") (pintype "unspecified"))
      (node (ref "R17") (pin "1") (pinfunction "1_1") (pintype "input"))
    )
    (net (code "28") (name "Net-(Q3-S)") (class "Default")
      (node (ref "Q3") (pin "2") (pinfunction "S_2") (pintype "unspecified"))
      (node (ref "R14") (pin "1") (pinfunction "1_1") (pintype "input"))
      (node (ref "U2") (pin "2") (pinfunction "GP1_2") (pintype "input"))
    )
    (net (code "29") (name "Net-(Q4-D)") (class "Default")
      (node (ref "CN1A") (pin "3") (pinfunction "3_3") (pintype "unspecified"))
      (node (ref "CN1B") (pin "3") (pinfunction "3_3") (pintype "unspecified"))
      (node (ref "Q4") (pin "3") (pinfunction "D_3") (pintype "unspecified"))
      (node (ref "R16") (pin "1") (pinfunction "1_1") (pintype "input"))
    )
    (net (code "30") (name "Net-(Q4-S)") (class "Default")
      (node (ref "Q4") (pin "2") (pinfunction "S_2") (pintype "unspecified"))
      (node (ref "R15") (pin "1") (pinfunction "1_1") (pintype "input"))
      (node (ref "U2") (pin "1") (pinfunction "GP0_1") (pintype "input"))
    )
    (net (code "31") (name "Net-(Q5-D)") (class "Default")
      (node (ref "Q5") (pin "3") (pinfunction "D_3") (pintype "unspecified"))
      (node (ref "R18") (pin "1") (pinfunction "1_1") (pintype "input"))
      (node (ref "SERVO") (pin "3") (pinfunction "3_3") (pintype "unspecified"))
    )
    (net (code "32") (name "Net-(Q5-S)") (class "Default")
      (node (ref "Q5") (pin "2") (pinfunction "S_2") (pintype "unspecified"))
      (node (ref "R19") (pin "1") (pinfunction "1_1") (pintype "input"))
      (node (ref "U2") (pin "9") (pinfunction "GP6_9") (pintype "input"))
    )
    (net (code "33") (name "Net-(Q6-B)") (class "Default")
      (node (ref "Q6") (pin "1") (pinfunction "B_1") (pintype "input"))
      (node (ref "R21") (pin "2") (pinfunction "2_2") (pintype "input"))
    )
    (net (code "34") (name "Net-(RESET-C)") (class "Default")
      (node (ref "RESET") (pin "3") (pinfunction "C_3") (pintype "unspecified"))
      (node (ref "U2") (pin "30") (pinfunction "RUN_30") (pintype "input"))
    )
    (net (code "35") (name "Net-(S1-B)") (class "Default")
      (node (ref "S1") (pin "2") (pinfunction "B_2") (pintype "unspecified"))
      (node (ref "U2") (pin "17") (pinfunction "GP13_17") (pintype "input"))
    )
    (net (code "36") (name "Net-(S2-B)") (class "Default")
      (node (ref "S2") (pin "2") (pinfunction "B_2") (pintype "unspecified"))
      (node (ref "U2") (pin "19") (pinfunction "GP14_19") (pintype "input"))
    )
    (net (code "37") (name "Net-(S3-B)") (class "Default")
      (node (ref "S3") (pin "2") (pinfunction "B_2") (pintype "unspecified"))
      (node (ref "U2") (pin "20") (pinfunction "GP15_20") (pintype "input"))
    )
    (net (code "38") (name "Net-(SW1-Anode)") (class "Default")
      (node (ref "R3") (pin "2") (pinfunction "2_2") (pintype "input"))
      (node (ref "SW1") (pin "4") (pinfunction "Anode_4") (pintype "unspecified"))
    )
    (net (code "39") (name "Net-(SW1-Collector)") (class "Default")
      (node (ref "R6") (pin "2") (pinfunction "2_2") (pintype "input"))
      (node (ref "SW1") (pin "2") (pinfunction "Collector_2") (pintype "unspecified"))
      (node (ref "U2") (pin "34") (pinfunction "GP28_34") (pintype "input"))
    )
    (net (code "40") (name "Net-(SW2-Anode)") (class "Default")
      (node (ref "R4") (pin "2") (pinfunction "2_2") (pintype "input"))
      (node (ref "SW2") (pin "4") (pinfunction "Anode_4") (pintype "unspecified"))
    )
    (net (code "41") (name "Net-(SW2-Collector)") (class "Default")
      (node (ref "R7") (pin "2") (pinfunction "2_2") (pintype "input"))
      (node (ref "SW2") (pin "2") (pinfunction "Collector_2") (pintype "unspecified"))
      (node (ref "U2") (pin "32") (pinfunction "GP27_32") (pintype "input"))
    )
    (net (code "42") (name "Net-(SW3-Anode)") (class "Default")
      (node (ref "R5") (pin "2") (pinfunction "2_2") (pintype "input"))
      (node (ref "SW3") (pin "4") (pinfunction "Anode_4") (pintype "unspecified"))
    )
    (net (code "43") (name "Net-(SW3-Collector)") (class "Default")
      (node (ref "R8") (pin "1") (pinfunction "1_1") (pintype "input"))
      (node (ref "SW3") (pin "2") (pinfunction "Collector_2") (pintype "unspecified"))
      (node (ref "U2") (pin "31") (pinfunction "GP26_31") (pintype "input"))
    )
    (net (code "44") (name "Net-(U1-EN)") (class "Default")
      (node (ref "C3") (pin "2") (pinfunction "2_2") (pintype "unspecified"))
      (node (ref "C4") (pin "2") (pinfunction "2_2") (pintype "unspecified"))
      (node (ref "U1") (pin "3") (pinfunction "VIN_3") (pintype "unspecified"))
      (node (ref "U1") (pin "5") (pinfunction "EN_5") (pintype "unspecified"))
      (node (ref "U10") (pin "3") (pinfunction "K_3") (pintype "unspecified"))
    )
    (net (code "45") (name "Net-(U1-SW)") (class "Default")
      (node (ref "C5") (pin "2") (pinfunction "2_2") (pintype "unspecified"))
      (node (ref "L1") (pin "1") (pinfunction "1_1") (pintype "unspecified"))
      (node (ref "U1") (pin "2") (pinfunction "SW_2") (pintype "unspecified"))
    )
    (net (code "46") (name "Net-(U1-VBST)") (class "Default")
      (node (ref "C5") (pin "1") (pinfunction "1_1") (pintype "unspecified"))
      (node (ref "U1") (pin "6") (pinfunction "VBST_6") (pintype "unspecified"))
    )
    (net (code "47") (name "Net-(U1-VFB)") (class "Default")
      (node (ref "R1") (pin "1") (pinfunction "1_1") (pintype "input"))
      (node (ref "R2") (pin "2") (pinfunction "2_2") (pintype "input"))
      (node (ref "U1") (pin "4") (pinfunction "VFB_4") (pintype "unspecified"))
    )
    (net (code "48") (name "Net-(U2-GP2)") (class "Default")
      (node (ref "CN2") (pin "3") (pinfunction "3_3") (pintype "unspecified"))
      (node (ref "U2") (pin "4") (pinfunction "GP2_4") (pintype "input"))
    )
    (net (code "49") (name "Net-(U2-GP3)") (class "Default")
      (node (ref "CN2") (pin "4") (pinfunction "4_4") (pintype "unspecified"))
      (node (ref "U2") (pin "5") (pinfunction "GP3_5") (pintype "input"))
    )
    (net (code "50") (name "Net-(U2-GP4)") (class "Default")
      (node (ref "CN3A") (pin "3") (pinfunction "3_3") (pintype "unspecified"))
      (node (ref "CN3B") (pin "3") (pinfunction "3_3") (pintype "unspecified"))
      (node (ref "U2") (pin "6") (pinfunction "GP4_6") (pintype "input"))
    )
    (net (code "51") (name "Net-(U2-GP5)") (class "Default")
      (node (ref "CN3A") (pin "4") (pinfunction "4_4") (pintype "unspecified"))
      (node (ref "CN3B") (pin "4") (pinfunction "4_4") (pintype "unspecified"))
      (node (ref "U2") (pin "7") (pinfunction "GP5_7") (pintype "input"))
    )
    (net (code "52") (name "Net-(U2-GP10)") (class "Default")
      (node (ref "R12") (pin "2") (pinfunction "2_2") (pintype "input"))
      (node (ref "U2") (pin "14") (pinfunction "GP10_14") (pintype "input"))
    )
    (net (code "53") (name "Net-(U2-GP11)") (class "Default")
      (node (ref "R13") (pin "2") (pinfunction "2_2") (pintype "input"))
      (node (ref "U2") (pin "15") (pinfunction "GP11_15") (pintype "input"))
    )
    (net (code "54") (name "Net-(U2-GP12)") (class "Default")
      (node (ref "U2") (pin "16") (pinfunction "GP12_16") (pintype "input"))
      (node (ref "U6") (pin "2") (pinfunction "A_2") (pintype "unspecified"))
    )
    (net (code "55") (name "Net-(U2-GP16)") (class "Default")
      (node (ref "U2") (pin "21") (pinfunction "GP16_21") (pintype "input"))
      (node (ref "U3") (pin "8") (pinfunction "DIR_8") (pintype "unspecified"))
    )
    (net (code "56") (name "Net-(U2-GP17)") (class "Default")
      (node (ref "U2") (pin "22") (pinfunction "GP17_22") (pintype "input"))
      (node (ref "U3") (pin "7") (pinfunction "STEP_7") (pintype "unspecified"))
    )
    (net (code "57") (name "Net-(U2-GP18)") (class "Default")
      (node (ref "U2") (pin "24") (pinfunction "GP18_24") (pintype "input"))
      (node (ref "U3") (pin "6") (pinfunction "SLP#_6") (pintype "unspecified"))
    )
    (net (code "58") (name "Net-(U2-GP19)") (class "Default")
      (node (ref "U2") (pin "25") (pinfunction "GP19_25") (pintype "input"))
      (node (ref "U4") (pin "8") (pinfunction "DIR_8") (pintype "unspecified"))
    )
    (net (code "59") (name "Net-(U2-GP20)") (class "Default")
      (node (ref "U2") (pin "26") (pinfunction "GP20_26") (pintype "input"))
      (node (ref "U4") (pin "7") (pinfunction "STEP_7") (pintype "unspecified"))
    )
    (net (code "60") (name "Net-(U2-GP21)") (class "Default")
      (node (ref "U2") (pin "27") (pinfunction "GP21_27") (pintype "input"))
      (node (ref "U4") (pin "6") (pinfunction "SLP#_6") (pintype "unspecified"))
    )
    (net (code "61") (name "Net-(U3-1A)") (class "Default")
      (node (ref "H4") (pin "3") (pinfunction "3_3") (pintype "unspecified"))
      (node (ref "U3") (pin "12") (pinfunction "1A_12") (pintype "unspecified"))
    )
    (net (code "62") (name "Net-(U3-1B)") (class "Default")
      (node (ref "H4") (pin "4") (pinfunction "4_4") (pintype "unspecified"))
      (node (ref "U3") (pin "11") (pinfunction "1B_11") (pintype "unspecified"))
    )
    (net (code "63") (name "Net-(U3-2A)") (class "Default")
      (node (ref "H4") (pin "2") (pinfunction "2_2") (pintype "unspecified"))
      (node (ref "U3") (pin "13") (pinfunction "2A_13") (pintype "unspecified"))
    )
    (net (code "64") (name "Net-(U3-2B)") (class "Default")
      (node (ref "H4") (pin "1") (pinfunction "1_1") (pintype "unspecified"))
      (node (ref "U3") (pin "14") (pinfunction "2B_14") (pintype "unspecified"))
    )
    (net (code "65") (name "Net-(U4-1A)") (class "Default")
      (node (ref "H3") (pin "3") (pinfunction "3_3") (pintype "unspecified"))
      (node (ref "U4") (pin "12") (pinfunction "1A_12") (pintype "unspecified"))
    )
    (net (code "66") (name "Net-(U4-1B)") (class "Default")
      (node (ref "H3") (pin "4") (pinfunction "4_4") (pintype "unspecified"))
      (node (ref "U4") (pin "11") (pinfunction "1B_11") (pintype "unspecified"))
    )
    (net (code "67") (name "Net-(U4-2A)") (class "Default")
      (node (ref "H3") (pin "2") (pinfunction "2_2") (pintype "unspecified"))
      (node (ref "U4") (pin "13") (pinfunction "2A_13") (pintype "unspecified"))
    )
    (net (code "68") (name "Net-(U4-2B)") (class "Default")
      (node (ref "H3") (pin "1") (pinfunction "1_1") (pintype "unspecified"))
      (node (ref "U4") (pin "14") (pinfunction "2B_14") (pintype "unspecified"))
    )
    (net (code "69") (name "Net-(U5-K)") (class "Default")
      (node (ref "R9") (pin "1") (pinfunction "1_1") (pintype "input"))
      (node (ref "U5") (pin "1") (pinfunction "K_1") (pintype "unspecified"))
    )
    (net (code "70") (name "Net-(U6-K)") (class "Default")
      (node (ref "R10") (pin "2") (pinfunction "2_2") (pintype "input"))
      (node (ref "U6") (pin "1") (pinfunction "K_1") (pintype "unspecified"))
    )
    (net (code "71") (name "RGB") (class "Default")
      (node (ref "LED1") (pin "4") (pinfunction "DIN_4") (pintype "unspecified"))
      (node (ref "U2") (pin "29") (pinfunction "GP22_29") (pintype "input"))
    )
    (net (code "72") (name "UIN") (class "Default")
      (node (ref "C10") (pin "1") (pinfunction "1_1") (pintype "input"))
      (node (ref "C11") (pin "1") (pinfunction "1_1") (pintype "input"))
      (node (ref "C12") (pin "1") (pinfunction "1_1") (pintype "input"))
      (node (ref "C13") (pin "1") (pinfunction "1_1") (pintype "input"))
      (node (ref "D1") (pin "1") (pinfunction "1_1") (pintype "unspecified"))
      (node (ref "D2") (pin "2") (pinfunction "2_2") (pintype "unspecified"))
      (node (ref "U3") (pin "16") (pinfunction "VMOT_16") (pintype "unspecified"))
      (node (ref "U4") (pin "16") (pinfunction "VMOT_16") (pintype "unspecified"))
      (node (ref "U9") (pin "3") (pinfunction "K_3") (pintype "unspecified"))
    )
    (net (code "73") (name "unconnected-(6050-AUX_CL-Pad7)") (class "Default")
      (node (ref "6050") (pin "7") (pinfunction "AUX_CL_7") (pintype "unspecified+no_connect"))
    )
    (net (code "74") (name "unconnected-(6050-AUX_DA-Pad6)") (class "Default")
      (node (ref "6050") (pin "6") (pinfunction "AUX_DA_6") (pintype "unspecified+no_connect"))
    )
    (net (code "75") (name "unconnected-(6050-EP-Pad25)") (class "Default")
      (node (ref "6050") (pin "25") (pinfunction "EP_25") (pintype "unspecified+no_connect"))
    )
    (net (code "76") (name "unconnected-(6050-NC-Pad2)") (class "Default")
      (node (ref "6050") (pin "2") (pinfunction "NC_2") (pintype "unspecified+no_connect"))
    )
    (net (code "77") (name "unconnected-(6050-NC-Pad3)") (class "Default")
      (node (ref "6050") (pin "3") (pinfunction "NC_3") (pintype "unspecified+no_connect"))
    )
    (net (code "78") (name "unconnected-(6050-NC-Pad4)") (class "Default")
      (node (ref "6050") (pin "4") (pinfunction "NC_4") (pintype "unspecified+no_connect"))
    )
    (net (code "79") (name "unconnected-(6050-NC-Pad5)") (class "Default")
      (node (ref "6050") (pin "5") (pinfunction "NC_5") (pintype "unspecified+no_connect"))
    )
    (net (code "80") (name "unconnected-(6050-NC-Pad14)") (class "Default")
      (node (ref "6050") (pin "14") (pinfunction "NC_14") (pintype "unspecified+no_connect"))
    )
    (net (code "81") (name "unconnected-(6050-NC-Pad15)") (class "Default")
      (node (ref "6050") (pin "15") (pinfunction "NC_15") (pintype "unspecified+no_connect"))
    )
    (net (code "82") (name "unconnected-(6050-NC-Pad16)") (class "Default")
      (node (ref "6050") (pin "16") (pinfunction "NC_16") (pintype "unspecified+no_connect"))
    )
    (net (code "83") (name "unconnected-(6050-NC-Pad17)") (class "Default")
      (node (ref "6050") (pin "17") (pinfunction "NC_17") (pintype "unspecified+no_connect"))
    )
    (net (code "84") (name "unconnected-(6050-RESV-Pad19)") (class "Default")
      (node (ref "6050") (pin "19") (pinfunction "RESV_19") (pintype "unspecified+no_connect"))
    )
    (net (code "85") (name "unconnected-(6050-RESV-Pad21)") (class "Default")
      (node (ref "6050") (pin "21") (pinfunction "RESV_21") (pintype "unspecified+no_connect"))
    )
    (net (code "86") (name "unconnected-(6050-RESV-Pad22)") (class "Default")
      (node (ref "6050") (pin "22") (pinfunction "RESV_22") (pintype "unspecified+no_connect"))
    )
    (net (code "87") (name "unconnected-(BUZZER-Pad3)") (class "Default")
      (node (ref "BUZZER") (pin "3") (pinfunction "3_3") (pintype "unspecified+no_connect"))
    )
    (net (code "88") (name "unconnected-(BUZZER-Pad4)") (class "Default")
      (node (ref "BUZZER") (pin "4") (pinfunction "4_4") (pintype "unspecified+no_connect"))
    )
    (net (code "89") (name "unconnected-(CN1A-Pad0)") (class "Default")
      (node (ref "CN1A") (pin "0") (pinfunction "0_0") (pintype "unspecified+no_connect"))
    )
    (net (code "90") (name "unconnected-(CN1B-Pad0)") (class "Default")
      (node (ref "CN1B") (pin "0") (pinfunction "0_0") (pintype "unspecified+no_connect"))
    )
    (net (code "91") (name "unconnected-(CN2-Pad0)") (class "Default")
      (node (ref "CN2") (pin "0") (pinfunction "0_0") (pintype "unspecified+no_connect"))
    )
    (net (code "92") (name "unconnected-(CN3A-Pad0)") (class "Default")
      (node (ref "CN3A") (pin "0") (pinfunction "0_0") (pintype "unspecified+no_connect"))
    )
    (net (code "93") (name "unconnected-(CN3B-Pad0)") (class "Default")
      (node (ref "CN3B") (pin "0") (pinfunction "0_0") (pintype "unspecified+no_connect"))
    )
    (net (code "94") (name "unconnected-(LED10-DOUT-Pad2)") (class "Default")
      (node (ref "LED10") (pin "2") (pinfunction "DOUT_2") (pintype "unspecified+no_connect"))
    )
    (net (code "95") (name "unconnected-(RESET-A-Pad1)") (class "Default")
      (node (ref "RESET") (pin "1") (pinfunction "A_1") (pintype "unspecified+no_connect"))
    )
    (net (code "96") (name "unconnected-(RESET-D-Pad4)") (class "Default")
      (node (ref "RESET") (pin "4") (pinfunction "D_4") (pintype "unspecified+no_connect"))
    )
    (net (code "97") (name "unconnected-(S1-A-Pad1)") (class "Default")
      (node (ref "S1") (pin "1") (pinfunction "A_1") (pintype "unspecified+no_connect"))
    )
    (net (code "98") (name "unconnected-(S1-D-Pad4)") (class "Default")
      (node (ref "S1") (pin "4") (pinfunction "D_4") (pintype "unspecified+no_connect"))
    )
    (net (code "99") (name "unconnected-(S2-A-Pad1)") (class "Default")
      (node (ref "S2") (pin "1") (pinfunction "A_1") (pintype "unspecified+no_connect"))
    )
    (net (code "100") (name "unconnected-(S2-D-Pad4)") (class "Default")
      (node (ref "S2") (pin "4") (pinfunction "D_4") (pintype "unspecified+no_connect"))
    )
    (net (code "101") (name "unconnected-(S3-A-Pad1)") (class "Default")
      (node (ref "S3") (pin "1") (pinfunction "A_1") (pintype "unspecified+no_connect"))
    )
    (net (code "102") (name "unconnected-(S3-D-Pad4)") (class "Default")
      (node (ref "S3") (pin "4") (pinfunction "D_4") (pintype "unspecified+no_connect"))
    )
    (net (code "103") (name "unconnected-(U2-3V3_EN-Pad37)") (class "Default")
      (node (ref "U2") (pin "37") (pinfunction "3V3_EN_37") (pintype "input+no_connect"))
    )
    (net (code "104") (name "unconnected-(U3-EN#-Pad1)") (class "Default")
      (node (ref "U3") (pin "1") (pinfunction "EN#_1") (pintype "unspecified+no_connect"))
    )
    (net (code "105") (name "unconnected-(U3-VDD-Pad10)") (class "Default")
      (node (ref "U3") (pin "10") (pinfunction "VDD_10") (pintype "unspecified+no_connect"))
    )
    (net (code "106") (name "unconnected-(U4-EN#-Pad1)") (class "Default")
      (node (ref "U4") (pin "1") (pinfunction "EN#_1") (pintype "unspecified+no_connect"))
    )
    (net (code "107") (name "unconnected-(U4-VDD-Pad10)") (class "Default")
      (node (ref "U4") (pin "10") (pinfunction "VDD_10") (pintype "unspecified+no_connect"))
    )
  )
)
